# 2021_Template_4_Layer.net
KiCad netlist of a schematic drawn in EAGLE
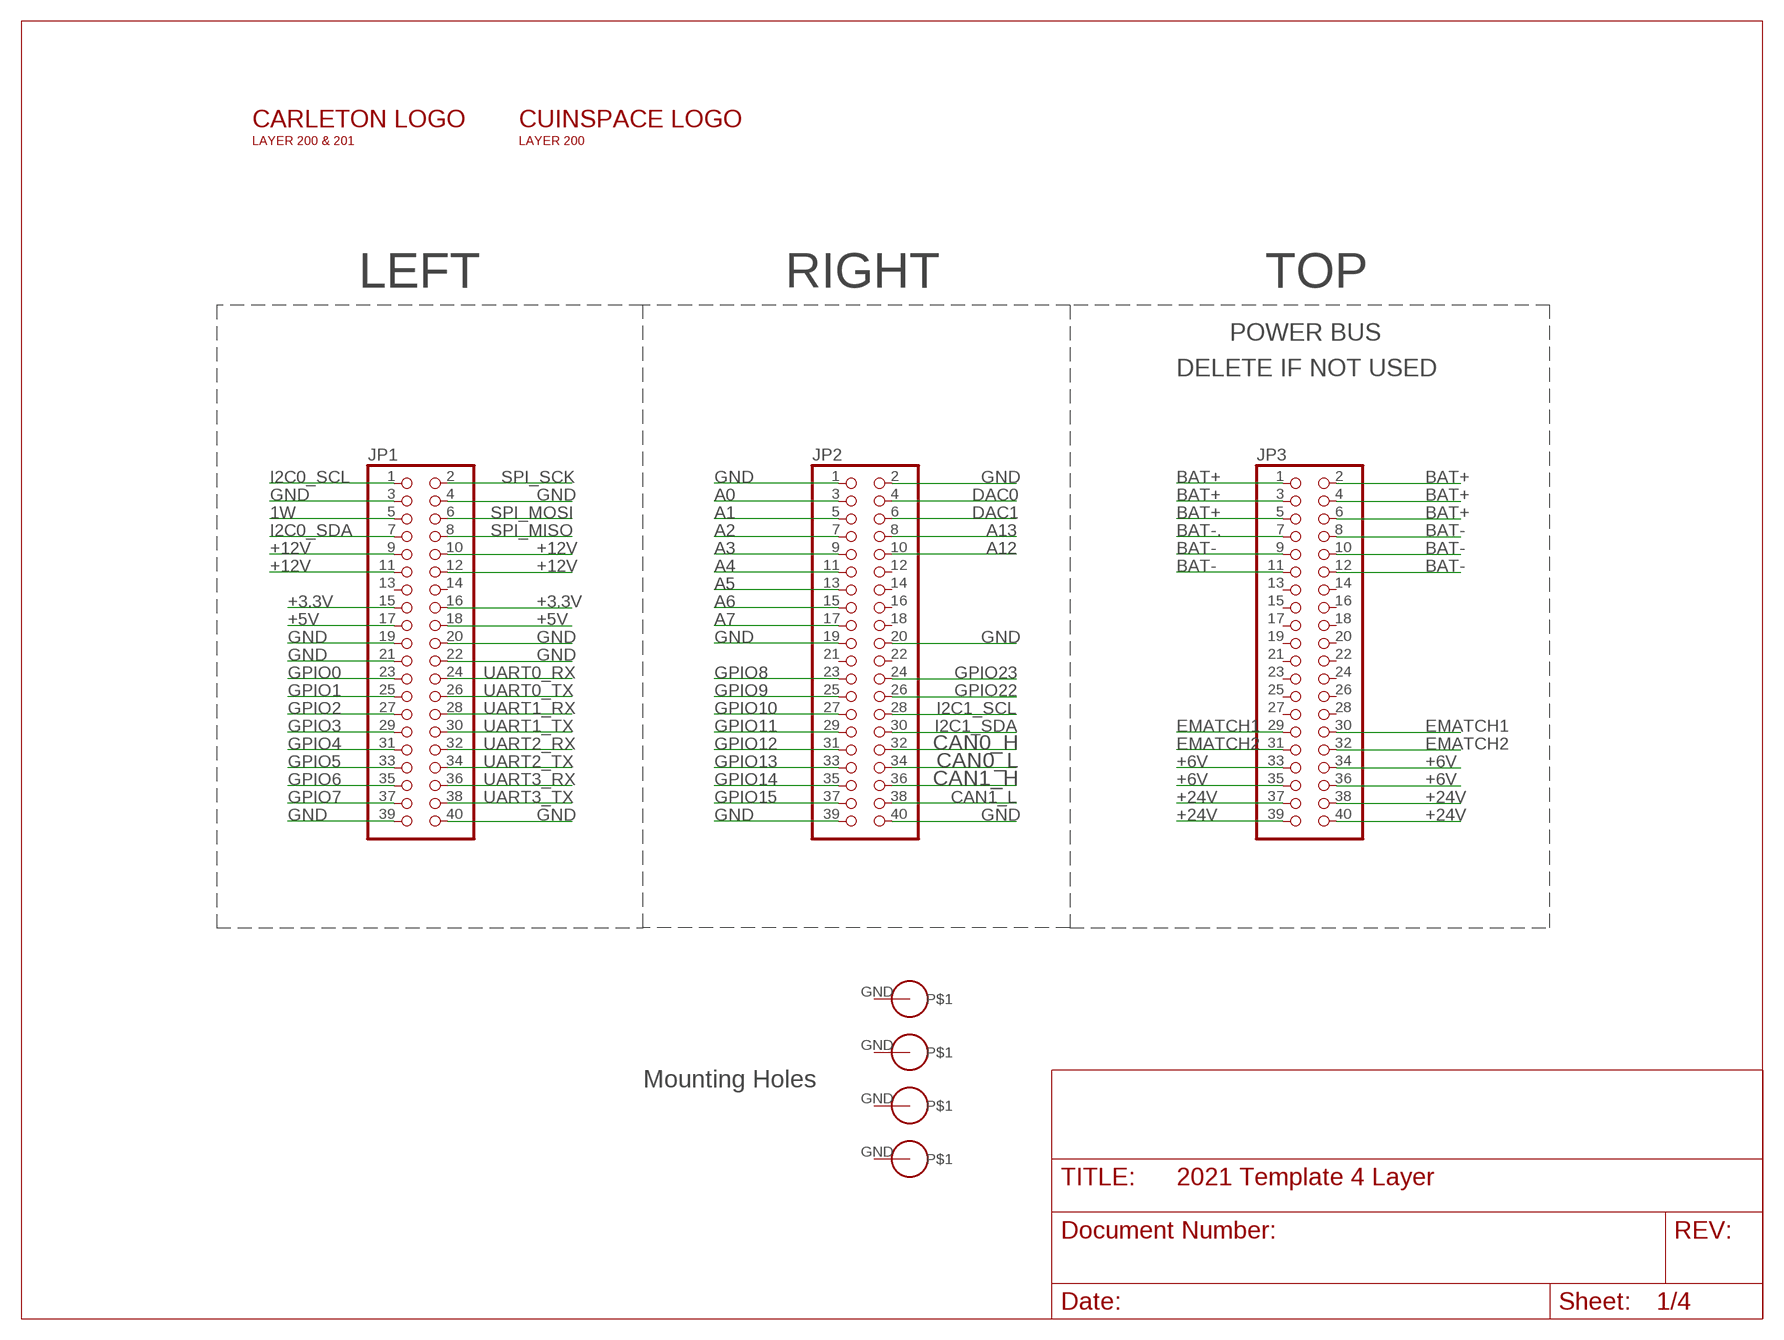
[diagram p0: schematic, sheet 1]
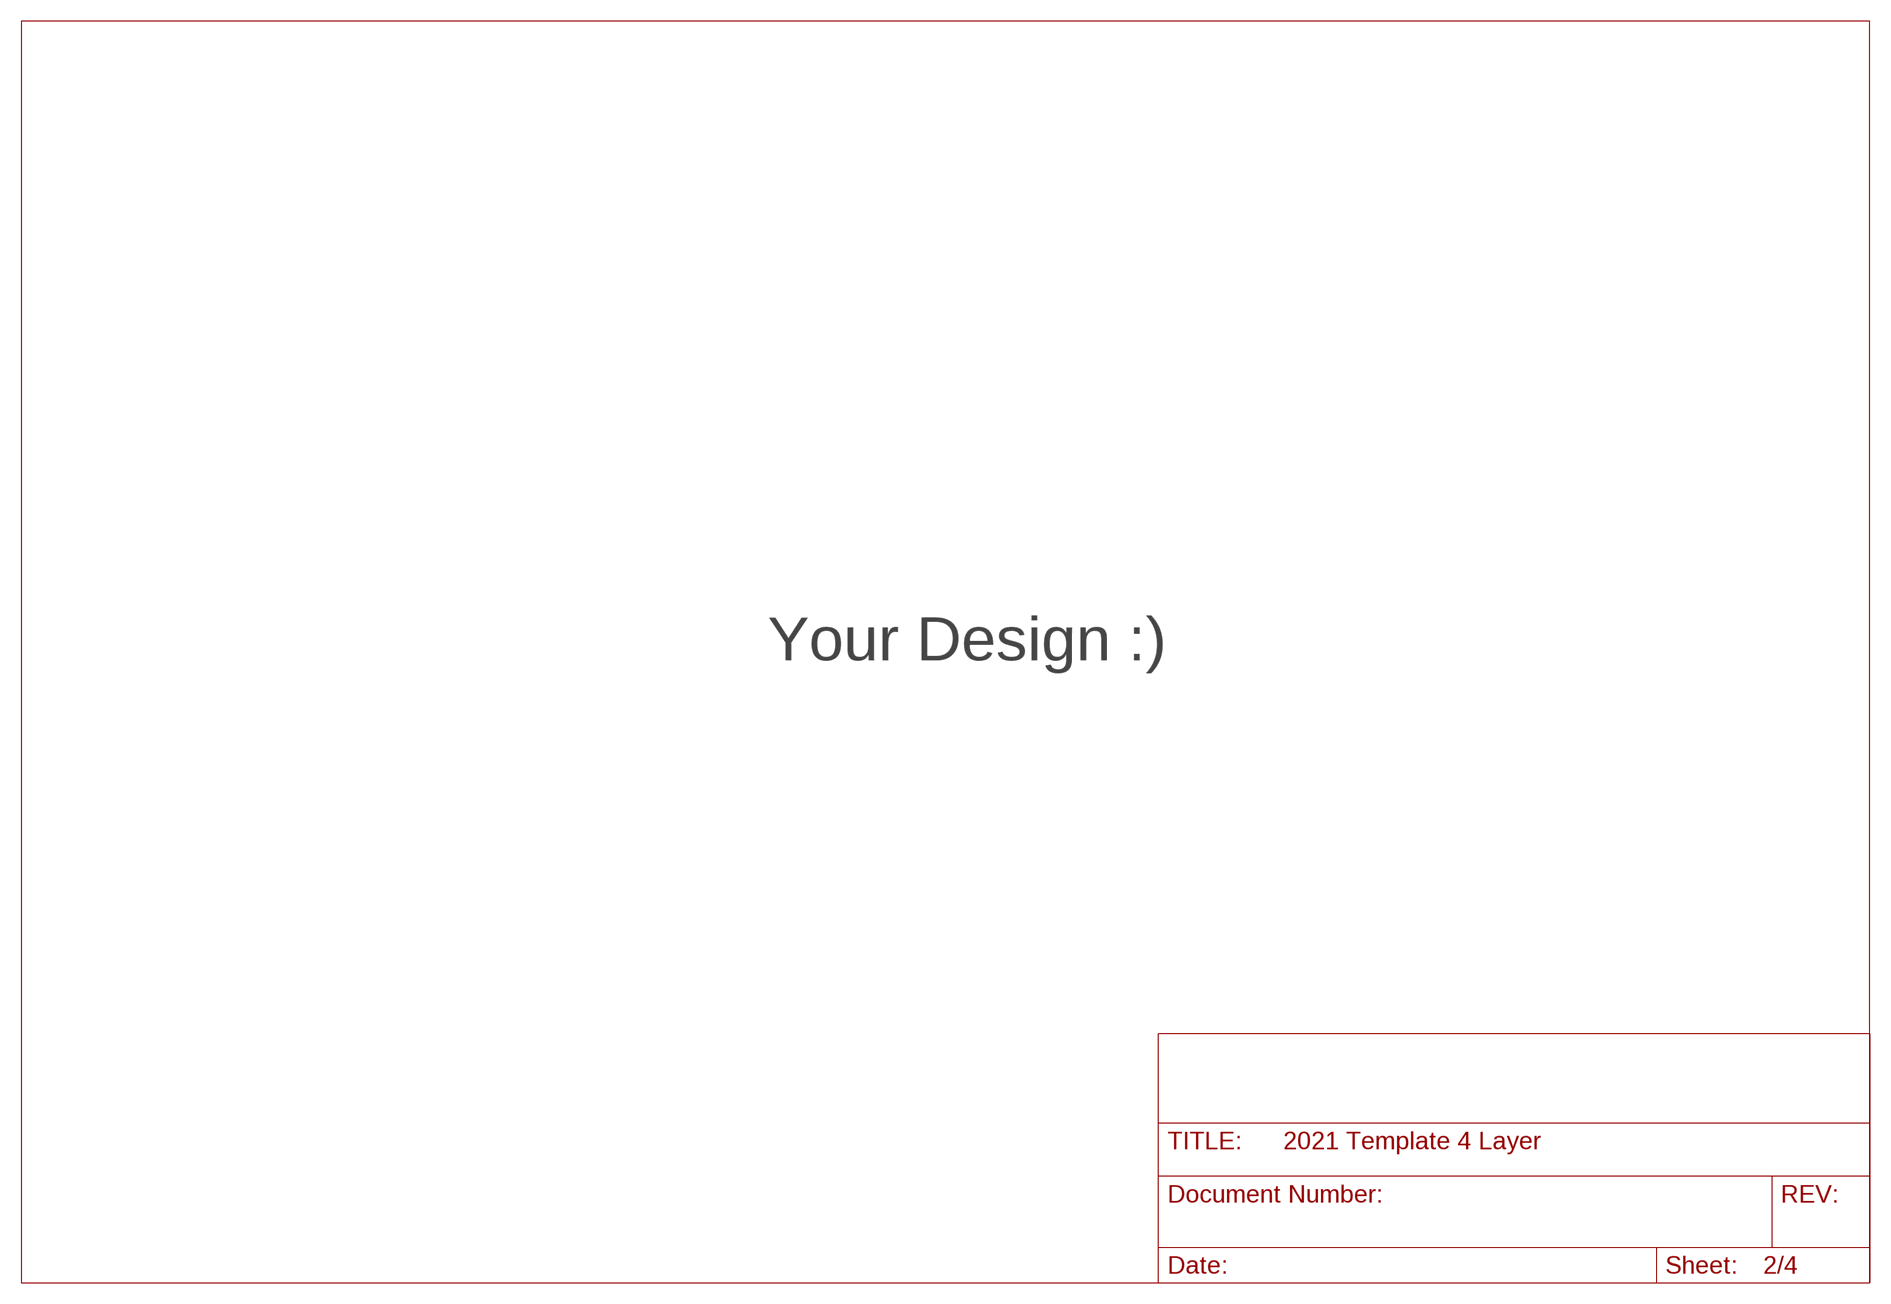
[diagram p1: schematic, sheet 2]

(export (version "E")
  (design (tool "Eeschema 10.0.6"))
  (components
    (comp (ref "$$U$1")
      (value "PS/104-MOUNTING-HOLE")
      (footprint "eagle-import:PC_104-MOUNTING-HOLE")
      (libsource (lib "eagle-import") (part "PS/104-MOUNTING-HOLE"))
    )
    (comp (ref "JP1")
      (value "PINHD-2X20")
      (footprint "eagle-import:2X20")
      (libsource (lib "eagle-import") (part "PINHD-2X20"))
    )
    (comp (ref "JP2")
      (value "PINHD-2X20")
      (footprint "eagle-import:2X20")
      (libsource (lib "eagle-import") (part "PINHD-2X20"))
    )
    (comp (ref "JP3")
      (value "PINHD-2X20")
      (footprint "eagle-import:2X20")
      (libsource (lib "eagle-import") (part "PINHD-2X20"))
    )
    (comp (ref "U$1")
      (value "PS/104-MOUNTING-HOLE")
      (footprint "eagle-import:PC_104-MOUNTING-HOLE")
      (libsource (lib "eagle-import") (part "PS/104-MOUNTING-HOLE"))
    )
    (comp (ref "U$2")
      (value "PS/104-MOUNTING-HOLE")
      (footprint "eagle-import:PC_104-MOUNTING-HOLE")
      (libsource (lib "eagle-import") (part "PS/104-MOUNTING-HOLE"))
    )
    (comp (ref "U$3")
      (value "PS/104-MOUNTING-HOLE")
      (footprint "eagle-import:PC_104-MOUNTING-HOLE")
      (libsource (lib "eagle-import") (part "PS/104-MOUNTING-HOLE"))
    )
    (comp (ref "U$4")
      (value "CARLETON3CM")
      (footprint "eagle-import:CARLETONU_3CM")
      (libsource (lib "eagle-import") (part "CARLETON3CM"))
    )
    (comp (ref "U$6")
      (value "INSPACE3CM_L")
      (footprint "eagle-import:INSPACE_3CM_LETTERS")
      (libsource (lib "eagle-import") (part "INSPACE3CM_L"))
    )
  )
  (nets
    (net (code "1") (name "+3.3V") (class "Default")
      (node (ref "JP1") (pin "15") (pinfunction "15_15") (pintype "passive"))
      (node (ref "JP1") (pin "16") (pinfunction "16_16") (pintype "passive"))
    )
    (net (code "2") (name "+5V") (class "Default")
      (node (ref "JP1") (pin "17") (pinfunction "17_17") (pintype "passive"))
      (node (ref "JP1") (pin "18") (pinfunction "18_18") (pintype "passive"))
    )
    (net (code "3") (name "+6V") (class "Default")
      (node (ref "JP3") (pin "33") (pinfunction "33_33") (pintype "passive"))
      (node (ref "JP3") (pin "34") (pinfunction "34_34") (pintype "passive"))
      (node (ref "JP3") (pin "35") (pinfunction "35_35") (pintype "passive"))
      (node (ref "JP3") (pin "36") (pinfunction "36_36") (pintype "passive"))
    )
    (net (code "4") (name "+12V") (class "Default")
      (node (ref "JP1") (pin "10") (pinfunction "10_10") (pintype "passive"))
      (node (ref "JP1") (pin "11") (pinfunction "11_11") (pintype "passive"))
      (node (ref "JP1") (pin "12") (pinfunction "12_12") (pintype "passive"))
      (node (ref "JP1") (pin "9") (pinfunction "9_9") (pintype "passive"))
    )
    (net (code "5") (name "+24V") (class "Default")
      (node (ref "JP3") (pin "37") (pinfunction "37_37") (pintype "passive"))
      (node (ref "JP3") (pin "38") (pinfunction "38_38") (pintype "passive"))
      (node (ref "JP3") (pin "39") (pinfunction "39_39") (pintype "passive"))
      (node (ref "JP3") (pin "40") (pinfunction "40_40") (pintype "passive"))
    )
    (net (code "6") (name "1W") (class "Default")
      (node (ref "JP1") (pin "5") (pinfunction "5_5") (pintype "passive"))
    )
    (net (code "7") (name "A0") (class "Default")
      (node (ref "JP2") (pin "3") (pinfunction "3_3") (pintype "passive"))
    )
    (net (code "8") (name "A1") (class "Default")
      (node (ref "JP2") (pin "5") (pinfunction "5_5") (pintype "passive"))
    )
    (net (code "9") (name "A2") (class "Default")
      (node (ref "JP2") (pin "7") (pinfunction "7_7") (pintype "passive"))
    )
    (net (code "10") (name "A3") (class "Default")
      (node (ref "JP2") (pin "9") (pinfunction "9_9") (pintype "passive"))
    )
    (net (code "11") (name "A4") (class "Default")
      (node (ref "JP2") (pin "11") (pinfunction "11_11") (pintype "passive"))
    )
    (net (code "12") (name "A5") (class "Default")
      (node (ref "JP2") (pin "13") (pinfunction "13_13") (pintype "passive"))
    )
    (net (code "13") (name "A6") (class "Default")
      (node (ref "JP2") (pin "15") (pinfunction "15_15") (pintype "passive"))
    )
    (net (code "14") (name "A7") (class "Default")
      (node (ref "JP2") (pin "17") (pinfunction "17_17") (pintype "passive"))
    )
    (net (code "15") (name "A12") (class "Default")
      (node (ref "JP2") (pin "10") (pinfunction "10_10") (pintype "passive"))
    )
    (net (code "16") (name "A13") (class "Default")
      (node (ref "JP2") (pin "8") (pinfunction "8_8") (pintype "passive"))
    )
    (net (code "17") (name "BAT+") (class "Default")
      (node (ref "JP3") (pin "1") (pinfunction "1_1") (pintype "passive"))
      (node (ref "JP3") (pin "2") (pinfunction "2_2") (pintype "passive"))
      (node (ref "JP3") (pin "3") (pinfunction "3_3") (pintype "passive"))
      (node (ref "JP3") (pin "4") (pinfunction "4_4") (pintype "passive"))
      (node (ref "JP3") (pin "5") (pinfunction "5_5") (pintype "passive"))
      (node (ref "JP3") (pin "6") (pinfunction "6_6") (pintype "passive"))
    )
    (net (code "18") (name "BAT-") (class "Default")
      (node (ref "JP3") (pin "10") (pinfunction "10_10") (pintype "passive"))
      (node (ref "JP3") (pin "11") (pinfunction "11_11") (pintype "passive"))
      (node (ref "JP3") (pin "12") (pinfunction "12_12") (pintype "passive"))
      (node (ref "JP3") (pin "8") (pinfunction "8_8") (pintype "passive"))
      (node (ref "JP3") (pin "9") (pinfunction "9_9") (pintype "passive"))
    )
    (net (code "19") (name "BAT-.") (class "Default")
      (node (ref "JP3") (pin "7") (pinfunction "7_7") (pintype "passive"))
    )
    (net (code "20") (name "CAN0_H") (class "Default")
      (node (ref "JP2") (pin "32") (pinfunction "32_32") (pintype "passive"))
    )
    (net (code "21") (name "CAN0_L") (class "Default")
      (node (ref "JP2") (pin "34") (pinfunction "34_34") (pintype "passive"))
    )
    (net (code "22") (name "CAN1_H") (class "Default")
      (node (ref "JP2") (pin "36") (pinfunction "36_36") (pintype "passive"))
    )
    (net (code "23") (name "CAN1_L") (class "Default")
      (node (ref "JP2") (pin "38") (pinfunction "38_38") (pintype "passive"))
    )
    (net (code "24") (name "DAC0") (class "Default")
      (node (ref "JP2") (pin "4") (pinfunction "4_4") (pintype "passive"))
    )
    (net (code "25") (name "DAC1") (class "Default")
      (node (ref "JP2") (pin "6") (pinfunction "6_6") (pintype "passive"))
    )
    (net (code "26") (name "EMATCH1") (class "Default")
      (node (ref "JP3") (pin "29") (pinfunction "29_29") (pintype "passive"))
      (node (ref "JP3") (pin "30") (pinfunction "30_30") (pintype "passive"))
    )
    (net (code "27") (name "EMATCH2") (class "Default")
      (node (ref "JP3") (pin "31") (pinfunction "31_31") (pintype "passive"))
      (node (ref "JP3") (pin "32") (pinfunction "32_32") (pintype "passive"))
    )
    (net (code "28") (name "GND") (class "Default")
      (node (ref "JP1") (pin "19") (pinfunction "19_19") (pintype "passive"))
      (node (ref "JP1") (pin "20") (pinfunction "20_20") (pintype "passive"))
      (node (ref "JP1") (pin "21") (pinfunction "21_21") (pintype "passive"))
      (node (ref "JP1") (pin "22") (pinfunction "22_22") (pintype "passive"))
      (node (ref "JP1") (pin "3") (pinfunction "3_3") (pintype "passive"))
      (node (ref "JP1") (pin "39") (pinfunction "39_39") (pintype "passive"))
      (node (ref "JP1") (pin "4") (pinfunction "4_4") (pintype "passive"))
      (node (ref "JP1") (pin "40") (pinfunction "40_40") (pintype "passive"))
      (node (ref "JP2") (pin "1") (pinfunction "1_1") (pintype "passive"))
      (node (ref "JP2") (pin "19") (pinfunction "19_19") (pintype "passive"))
      (node (ref "JP2") (pin "2") (pinfunction "2_2") (pintype "passive"))
      (node (ref "JP2") (pin "20") (pinfunction "20_20") (pintype "passive"))
      (node (ref "JP2") (pin "39") (pinfunction "39_39") (pintype "passive"))
      (node (ref "JP2") (pin "40") (pinfunction "40_40") (pintype "passive"))
    )
    (net (code "29") (name "GPIO0") (class "Default")
      (node (ref "JP1") (pin "23") (pinfunction "23_23") (pintype "passive"))
    )
    (net (code "30") (name "GPIO1") (class "Default")
      (node (ref "JP1") (pin "25") (pinfunction "25_25") (pintype "passive"))
    )
    (net (code "31") (name "GPIO2") (class "Default")
      (node (ref "JP1") (pin "27") (pinfunction "27_27") (pintype "passive"))
    )
    (net (code "32") (name "GPIO3") (class "Default")
      (node (ref "JP1") (pin "29") (pinfunction "29_29") (pintype "passive"))
    )
    (net (code "33") (name "GPIO4") (class "Default")
      (node (ref "JP1") (pin "31") (pinfunction "31_31") (pintype "passive"))
    )
    (net (code "34") (name "GPIO5") (class "Default")
      (node (ref "JP1") (pin "33") (pinfunction "33_33") (pintype "passive"))
    )
    (net (code "35") (name "GPIO6") (class "Default")
      (node (ref "JP1") (pin "35") (pinfunction "35_35") (pintype "passive"))
    )
    (net (code "36") (name "GPIO7") (class "Default")
      (node (ref "JP1") (pin "37") (pinfunction "37_37") (pintype "passive"))
    )
    (net (code "37") (name "GPIO8") (class "Default")
      (node (ref "JP2") (pin "23") (pinfunction "23_23") (pintype "passive"))
    )
    (net (code "38") (name "GPIO9") (class "Default")
      (node (ref "JP2") (pin "25") (pinfunction "25_25") (pintype "passive"))
    )
    (net (code "39") (name "GPIO10") (class "Default")
      (node (ref "JP2") (pin "27") (pinfunction "27_27") (pintype "passive"))
    )
    (net (code "40") (name "GPIO11") (class "Default")
      (node (ref "JP2") (pin "29") (pinfunction "29_29") (pintype "passive"))
    )
    (net (code "41") (name "GPIO12") (class "Default")
      (node (ref "JP2") (pin "31") (pinfunction "31_31") (pintype "passive"))
    )
    (net (code "42") (name "GPIO13") (class "Default")
      (node (ref "JP2") (pin "33") (pinfunction "33_33") (pintype "passive"))
    )
    (net (code "43") (name "GPIO14") (class "Default")
      (node (ref "JP2") (pin "35") (pinfunction "35_35") (pintype "passive"))
    )
    (net (code "44") (name "GPIO15") (class "Default")
      (node (ref "JP2") (pin "37") (pinfunction "37_37") (pintype "passive"))
    )
    (net (code "45") (name "GPIO22") (class "Default")
      (node (ref "JP2") (pin "26") (pinfunction "26_26") (pintype "passive"))
    )
    (net (code "46") (name "GPIO23") (class "Default")
      (node (ref "JP2") (pin "24") (pinfunction "24_24") (pintype "passive"))
    )
    (net (code "47") (name "I2C0_SCL") (class "Default")
      (node (ref "JP1") (pin "1") (pinfunction "1_1") (pintype "passive"))
    )
    (net (code "48") (name "I2C0_SDA") (class "Default")
      (node (ref "JP1") (pin "7") (pinfunction "7_7") (pintype "passive"))
    )
    (net (code "49") (name "I2C1_SCL") (class "Default")
      (node (ref "JP2") (pin "28") (pinfunction "28_28") (pintype "passive"))
    )
    (net (code "50") (name "I2C1_SDA") (class "Default")
      (node (ref "JP2") (pin "30") (pinfunction "30_30") (pintype "passive"))
    )
    (net (code "51") (name "SPI_MISO") (class "Default")
      (node (ref "JP1") (pin "8") (pinfunction "8_8") (pintype "passive"))
    )
    (net (code "52") (name "SPI_MOSI") (class "Default")
      (node (ref "JP1") (pin "6") (pinfunction "6_6") (pintype "passive"))
    )
    (net (code "53") (name "SPI_SCK") (class "Default")
      (node (ref "JP1") (pin "2") (pinfunction "2_2") (pintype "passive"))
    )
    (net (code "54") (name "UART0_RX") (class "Default")
      (node (ref "JP1") (pin "24") (pinfunction "24_24") (pintype "passive"))
    )
    (net (code "55") (name "UART0_TX") (class "Default")
      (node (ref "JP1") (pin "26") (pinfunction "26_26") (pintype "passive"))
    )
    (net (code "56") (name "UART1_RX") (class "Default")
      (node (ref "JP1") (pin "28") (pinfunction "28_28") (pintype "passive"))
    )
    (net (code "57") (name "UART1_TX") (class "Default")
      (node (ref "JP1") (pin "30") (pinfunction "30_30") (pintype "passive"))
    )
    (net (code "58") (name "UART2_RX") (class "Default")
      (node (ref "JP1") (pin "32") (pinfunction "32_32") (pintype "passive"))
    )
    (net (code "59") (name "UART2_TX") (class "Default")
      (node (ref "JP1") (pin "34") (pinfunction "34_34") (pintype "passive"))
    )
    (net (code "60") (name "UART3_RX") (class "Default")
      (node (ref "JP1") (pin "36") (pinfunction "36_36") (pintype "passive"))
    )
    (net (code "61") (name "UART3_TX") (class "Default")
      (node (ref "JP1") (pin "38") (pinfunction "38_38") (pintype "passive"))
    )
    (net (code "62") (name "unconnected-($$U$1-P$1-PadGND)") (class "Default")
      (node (ref "$$U$1") (pin "GND") (pinfunction "P$1_GND") (pintype "bidirectional"))
    )
    (net (code "63") (name "unconnected-(JP1-Pad13)") (class "Default")
      (node (ref "JP1") (pin "13") (pinfunction "13_13") (pintype "passive"))
    )
    (net (code "64") (name "unconnected-(JP1-Pad14)") (class "Default")
      (node (ref "JP1") (pin "14") (pinfunction "14_14") (pintype "passive"))
    )
    (net (code "65") (name "unconnected-(JP2-Pad12)") (class "Default")
      (node (ref "JP2") (pin "12") (pinfunction "12_12") (pintype "passive"))
    )
    (net (code "66") (name "unconnected-(JP2-Pad14)") (class "Default")
      (node (ref "JP2") (pin "14") (pinfunction "14_14") (pintype "passive"))
    )
    (net (code "67") (name "unconnected-(JP2-Pad16)") (class "Default")
      (node (ref "JP2") (pin "16") (pinfunction "16_16") (pintype "passive"))
    )
    (net (code "68") (name "unconnected-(JP2-Pad18)") (class "Default")
      (node (ref "JP2") (pin "18") (pinfunction "18_18") (pintype "passive"))
    )
    (net (code "69") (name "unconnected-(JP2-Pad21)") (class "Default")
      (node (ref "JP2") (pin "21") (pinfunction "21_21") (pintype "passive"))
    )
    (net (code "70") (name "unconnected-(JP2-Pad22)") (class "Default")
      (node (ref "JP2") (pin "22") (pinfunction "22_22") (pintype "passive"))
    )
    (net (code "71") (name "unconnected-(JP3-Pad13)") (class "Default")
      (node (ref "JP3") (pin "13") (pinfunction "13_13") (pintype "passive"))
    )
    (net (code "72") (name "unconnected-(JP3-Pad14)") (class "Default")
      (node (ref "JP3") (pin "14") (pinfunction "14_14") (pintype "passive"))
    )
    (net (code "73") (name "unconnected-(JP3-Pad15)") (class "Default")
      (node (ref "JP3") (pin "15") (pinfunction "15_15") (pintype "passive"))
    )
    (net (code "74") (name "unconnected-(JP3-Pad16)") (class "Default")
      (node (ref "JP3") (pin "16") (pinfunction "16_16") (pintype "passive"))
    )
    (net (code "75") (name "unconnected-(JP3-Pad17)") (class "Default")
      (node (ref "JP3") (pin "17") (pinfunction "17_17") (pintype "passive"))
    )
    (net (code "76") (name "unconnected-(JP3-Pad18)") (class "Default")
      (node (ref "JP3") (pin "18") (pinfunction "18_18") (pintype "passive"))
    )
    (net (code "77") (name "unconnected-(JP3-Pad19)") (class "Default")
      (node (ref "JP3") (pin "19") (pinfunction "19_19") (pintype "passive"))
    )
    (net (code "78") (name "unconnected-(JP3-Pad20)") (class "Default")
      (node (ref "JP3") (pin "20") (pinfunction "20_20") (pintype "passive"))
    )
    (net (code "79") (name "unconnected-(JP3-Pad21)") (class "Default")
      (node (ref "JP3") (pin "21") (pinfunction "21_21") (pintype "passive"))
    )
    (net (code "80") (name "unconnected-(JP3-Pad22)") (class "Default")
      (node (ref "JP3") (pin "22") (pinfunction "22_22") (pintype "passive"))
    )
    (net (code "81") (name "unconnected-(JP3-Pad23)") (class "Default")
      (node (ref "JP3") (pin "23") (pinfunction "23_23") (pintype "passive"))
    )
    (net (code "82") (name "unconnected-(JP3-Pad24)") (class "Default")
      (node (ref "JP3") (pin "24") (pinfunction "24_24") (pintype "passive"))
    )
    (net (code "83") (name "unconnected-(JP3-Pad25)") (class "Default")
      (node (ref "JP3") (pin "25") (pinfunction "25_25") (pintype "passive"))
    )
    (net (code "84") (name "unconnected-(JP3-Pad26)") (class "Default")
      (node (ref "JP3") (pin "26") (pinfunction "26_26") (pintype "passive"))
    )
    (net (code "85") (name "unconnected-(JP3-Pad27)") (class "Default")
      (node (ref "JP3") (pin "27") (pinfunction "27_27") (pintype "passive"))
    )
    (net (code "86") (name "unconnected-(JP3-Pad28)") (class "Default")
      (node (ref "JP3") (pin "28") (pinfunction "28_28") (pintype "passive"))
    )
    (net (code "87") (name "unconnected-(U$1-P$1-PadGND)") (class "Default")
      (node (ref "U$1") (pin "GND") (pinfunction "P$1_GND") (pintype "bidirectional"))
    )
    (net (code "88") (name "unconnected-(U$2-P$1-PadGND)") (class "Default")
      (node (ref "U$2") (pin "GND") (pinfunction "P$1_GND") (pintype "bidirectional"))
    )
    (net (code "89") (name "unconnected-(U$3-P$1-PadGND)") (class "Default")
      (node (ref "U$3") (pin "GND") (pinfunction "P$1_GND") (pintype "bidirectional"))
    )
  )
)
